# schematic.net
KiCad netlist of a schematic drawn in Altium Designer
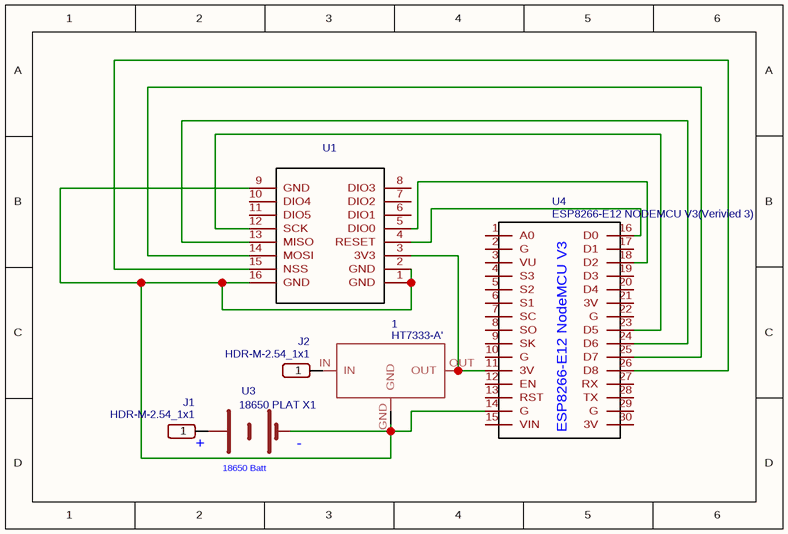
[diagram p0: schematic.schdoc]

(export (version "E")
  (design (tool "Eeschema 10.0.6"))
  (components
    (comp (ref "1")
      (value "HT7333-A'")
      (fields (field (name "CONTRIBUTOR") "userweb"))
      (libsource (lib "altium-import") (part "root_0_HT7333-A'_"))
    )
    (comp (ref "J1")
      (value "HDR-M-2.54_1x1")
      (fields (field (name "CONTRIBUTOR") "LCEDA_Lib"))
      (libsource (lib "altium-import") (part "root_0_HDR-M-2.54_1x1_"))
    )
    (comp (ref "J2")
      (value "HDR-M-2.54_1x1")
      (fields (field (name "CONTRIBUTOR") "LCEDA_Lib"))
      (libsource (lib "altium-import") (part "root_0_HDR-M-2.54_1x1_"))
    )
    (comp (ref "U1")
      (value "NO")
      (fields (field (name "CONTRIBUTOR") "nuttphong.sa"))
      (libsource (lib "altium-import") (part "root_2_NO_"))
    )
    (comp (ref "U3")
      (value "18650 PLAT X1")
      (fields (field (name "CONTRIBUTOR") "Andre C"))
      (libsource (lib "altium-import") (part "root_0_18650 PLAT X1_"))
    )
    (comp (ref "U4")
      (value "ESP8266-E12 NODEMCU V3(Verivied 3)")
      (fields (field (name "CONTRIBUTOR") "affanvb6"))
      (libsource (lib "altium-import") (part "root_0_ESP8266-E12 NODEMCU V3(Verivied 3)_"))
    )
  )
  (nets
    (net (code "1") (name "Net-(1-PadIN)") (class "Default")
      (node (ref "1") (pin "IN") (pinfunction "IN_IN") (pintype "passive"))
      (node (ref "J2") (pin "1") (pinfunction "1_1") (pintype "passive"))
    )
    (net (code "2") (name "Net-(U1-3V3)") (class "Default")
      (node (ref "1") (pin "OUT") (pinfunction "OUT_OUT") (pintype "passive"))
      (node (ref "U1") (pin "3") (pinfunction "3V3_3") (pintype "passive"))
      (node (ref "U4") (pin "11") (pinfunction "3V_11") (pintype "passive"))
    )
    (net (code "3") (name "Net-(U1-DIO0)") (class "Default")
      (node (ref "U1") (pin "5") (pinfunction "DIO0_5") (pintype "passive"))
      (node (ref "U4") (pin "18") (pinfunction "D2_18") (pintype "passive"))
    )
    (net (code "4") (name "Net-(U1-MISO)") (class "Default")
      (node (ref "U1") (pin "13") (pinfunction "MISO_13") (pintype "passive"))
      (node (ref "U4") (pin "24") (pinfunction "D6_24") (pintype "passive"))
    )
    (net (code "5") (name "Net-(U1-MOSI)") (class "Default")
      (node (ref "U1") (pin "14") (pinfunction "MOSI_14") (pintype "passive"))
      (node (ref "U4") (pin "25") (pinfunction "D7_25") (pintype "passive"))
    )
    (net (code "6") (name "Net-(U1-NSS)") (class "Default")
      (node (ref "U1") (pin "15") (pinfunction "NSS_15") (pintype "passive"))
      (node (ref "U4") (pin "26") (pinfunction "D8_26") (pintype "passive"))
    )
    (net (code "7") (name "Net-(U1-RESET)") (class "Default")
      (node (ref "U1") (pin "4") (pinfunction "RESET_4") (pintype "passive"))
      (node (ref "U4") (pin "16") (pinfunction "D0_16") (pintype "passive"))
    )
    (net (code "8") (name "Net-(U1-SCK)") (class "Default")
      (node (ref "U1") (pin "12") (pinfunction "SCK_12") (pintype "passive"))
      (node (ref "U4") (pin "23") (pinfunction "D5_23") (pintype "passive"))
    )
    (net (code "9") (name "Net-(U3-+)") (class "Default")
      (node (ref "J1") (pin "1") (pinfunction "1_1") (pintype "passive"))
      (node (ref "U3") (pin "1") (pinfunction "+_1") (pintype "passive"))
    )
    (net (code "10") (name "Net-(U3--)") (class "Default")
      (node (ref "1") (pin "GND") (pinfunction "GND_GND") (pintype "passive"))
      (node (ref "U1") (pin "1") (pinfunction "GND_1") (pintype "passive"))
      (node (ref "U1") (pin "16") (pinfunction "GND_16") (pintype "passive"))
      (node (ref "U1") (pin "2") (pinfunction "GND_2") (pintype "passive"))
      (node (ref "U1") (pin "9") (pinfunction "GND_9") (pintype "passive"))
      (node (ref "U3") (pin "2") (pinfunction "-_2") (pintype "passive"))
      (node (ref "U4") (pin "14") (pinfunction "G_14") (pintype "passive"))
    )
    (net (code "11") (name "unconnected-(U1-DIO1-Pad6)") (class "Default")
      (node (ref "U1") (pin "6") (pinfunction "DIO1_6") (pintype "passive"))
    )
    (net (code "12") (name "unconnected-(U1-DIO2-Pad7)") (class "Default")
      (node (ref "U1") (pin "7") (pinfunction "DIO2_7") (pintype "passive"))
    )
    (net (code "13") (name "unconnected-(U1-DIO3-Pad8)") (class "Default")
      (node (ref "U1") (pin "8") (pinfunction "DIO3_8") (pintype "passive"))
    )
    (net (code "14") (name "unconnected-(U1-DIO4-Pad10)") (class "Default")
      (node (ref "U1") (pin "10") (pinfunction "DIO4_10") (pintype "passive"))
    )
    (net (code "15") (name "unconnected-(U1-DIO5-Pad11)") (class "Default")
      (node (ref "U1") (pin "11") (pinfunction "DIO5_11") (pintype "passive"))
    )
    (net (code "16") (name "unconnected-(U4-3V-Pad21)") (class "Default")
      (node (ref "U4") (pin "21") (pinfunction "3V_21") (pintype "passive"))
    )
    (net (code "17") (name "unconnected-(U4-3V-Pad30)") (class "Default")
      (node (ref "U4") (pin "30") (pinfunction "3V_30") (pintype "passive"))
    )
    (net (code "18") (name "unconnected-(U4-A0-Pad1)") (class "Default")
      (node (ref "U4") (pin "1") (pinfunction "A0_1") (pintype "passive"))
    )
    (net (code "19") (name "unconnected-(U4-D1-Pad17)") (class "Default")
      (node (ref "U4") (pin "17") (pinfunction "D1_17") (pintype "passive"))
    )
    (net (code "20") (name "unconnected-(U4-D3-Pad19)") (class "Default")
      (node (ref "U4") (pin "19") (pinfunction "D3_19") (pintype "passive"))
    )
    (net (code "21") (name "unconnected-(U4-D4-Pad20)") (class "Default")
      (node (ref "U4") (pin "20") (pinfunction "D4_20") (pintype "passive"))
    )
    (net (code "22") (name "unconnected-(U4-EN-Pad12)") (class "Default")
      (node (ref "U4") (pin "12") (pinfunction "EN_12") (pintype "passive"))
    )
    (net (code "23") (name "unconnected-(U4-G-Pad2)") (class "Default")
      (node (ref "U4") (pin "2") (pinfunction "G_2") (pintype "passive"))
    )
    (net (code "24") (name "unconnected-(U4-G-Pad10)") (class "Default")
      (node (ref "U4") (pin "10") (pinfunction "G_10") (pintype "passive"))
    )
    (net (code "25") (name "unconnected-(U4-G-Pad22)") (class "Default")
      (node (ref "U4") (pin "22") (pinfunction "G_22") (pintype "passive"))
    )
    (net (code "26") (name "unconnected-(U4-G-Pad29)") (class "Default")
      (node (ref "U4") (pin "29") (pinfunction "G_29") (pintype "passive"))
    )
    (net (code "27") (name "unconnected-(U4-RST-Pad13)") (class "Default")
      (node (ref "U4") (pin "13") (pinfunction "RST_13") (pintype "passive"))
    )
    (net (code "28") (name "unconnected-(U4-RX-Pad27)") (class "Default")
      (node (ref "U4") (pin "27") (pinfunction "RX_27") (pintype "passive"))
    )
    (net (code "29") (name "unconnected-(U4-S1-Pad6)") (class "Default")
      (node (ref "U4") (pin "6") (pinfunction "S1_6") (pintype "passive"))
    )
    (net (code "30") (name "unconnected-(U4-S2-Pad5)") (class "Default")
      (node (ref "U4") (pin "5") (pinfunction "S2_5") (pintype "passive"))
    )
    (net (code "31") (name "unconnected-(U4-S3-Pad4)") (class "Default")
      (node (ref "U4") (pin "4") (pinfunction "S3_4") (pintype "passive"))
    )
    (net (code "32") (name "unconnected-(U4-SC-Pad7)") (class "Default")
      (node (ref "U4") (pin "7") (pinfunction "SC_7") (pintype "passive"))
    )
    (net (code "33") (name "unconnected-(U4-SK-Pad9)") (class "Default")
      (node (ref "U4") (pin "9") (pinfunction "SK_9") (pintype "passive"))
    )
    (net (code "34") (name "unconnected-(U4-SO-Pad8)") (class "Default")
      (node (ref "U4") (pin "8") (pinfunction "SO_8") (pintype "passive"))
    )
    (net (code "35") (name "unconnected-(U4-TX-Pad28)") (class "Default")
      (node (ref "U4") (pin "28") (pinfunction "TX_28") (pintype "passive"))
    )
    (net (code "36") (name "unconnected-(U4-VIN-Pad15)") (class "Default")
      (node (ref "U4") (pin "15") (pinfunction "VIN_15") (pintype "passive"))
    )
    (net (code "37") (name "unconnected-(U4-VU-Pad3)") (class "Default")
      (node (ref "U4") (pin "3") (pinfunction "VU_3") (pintype "passive"))
    )
  )
)
